# Shield_V4_Connector_All.net
KiCad netlist of a schematic drawn in EasyEDA
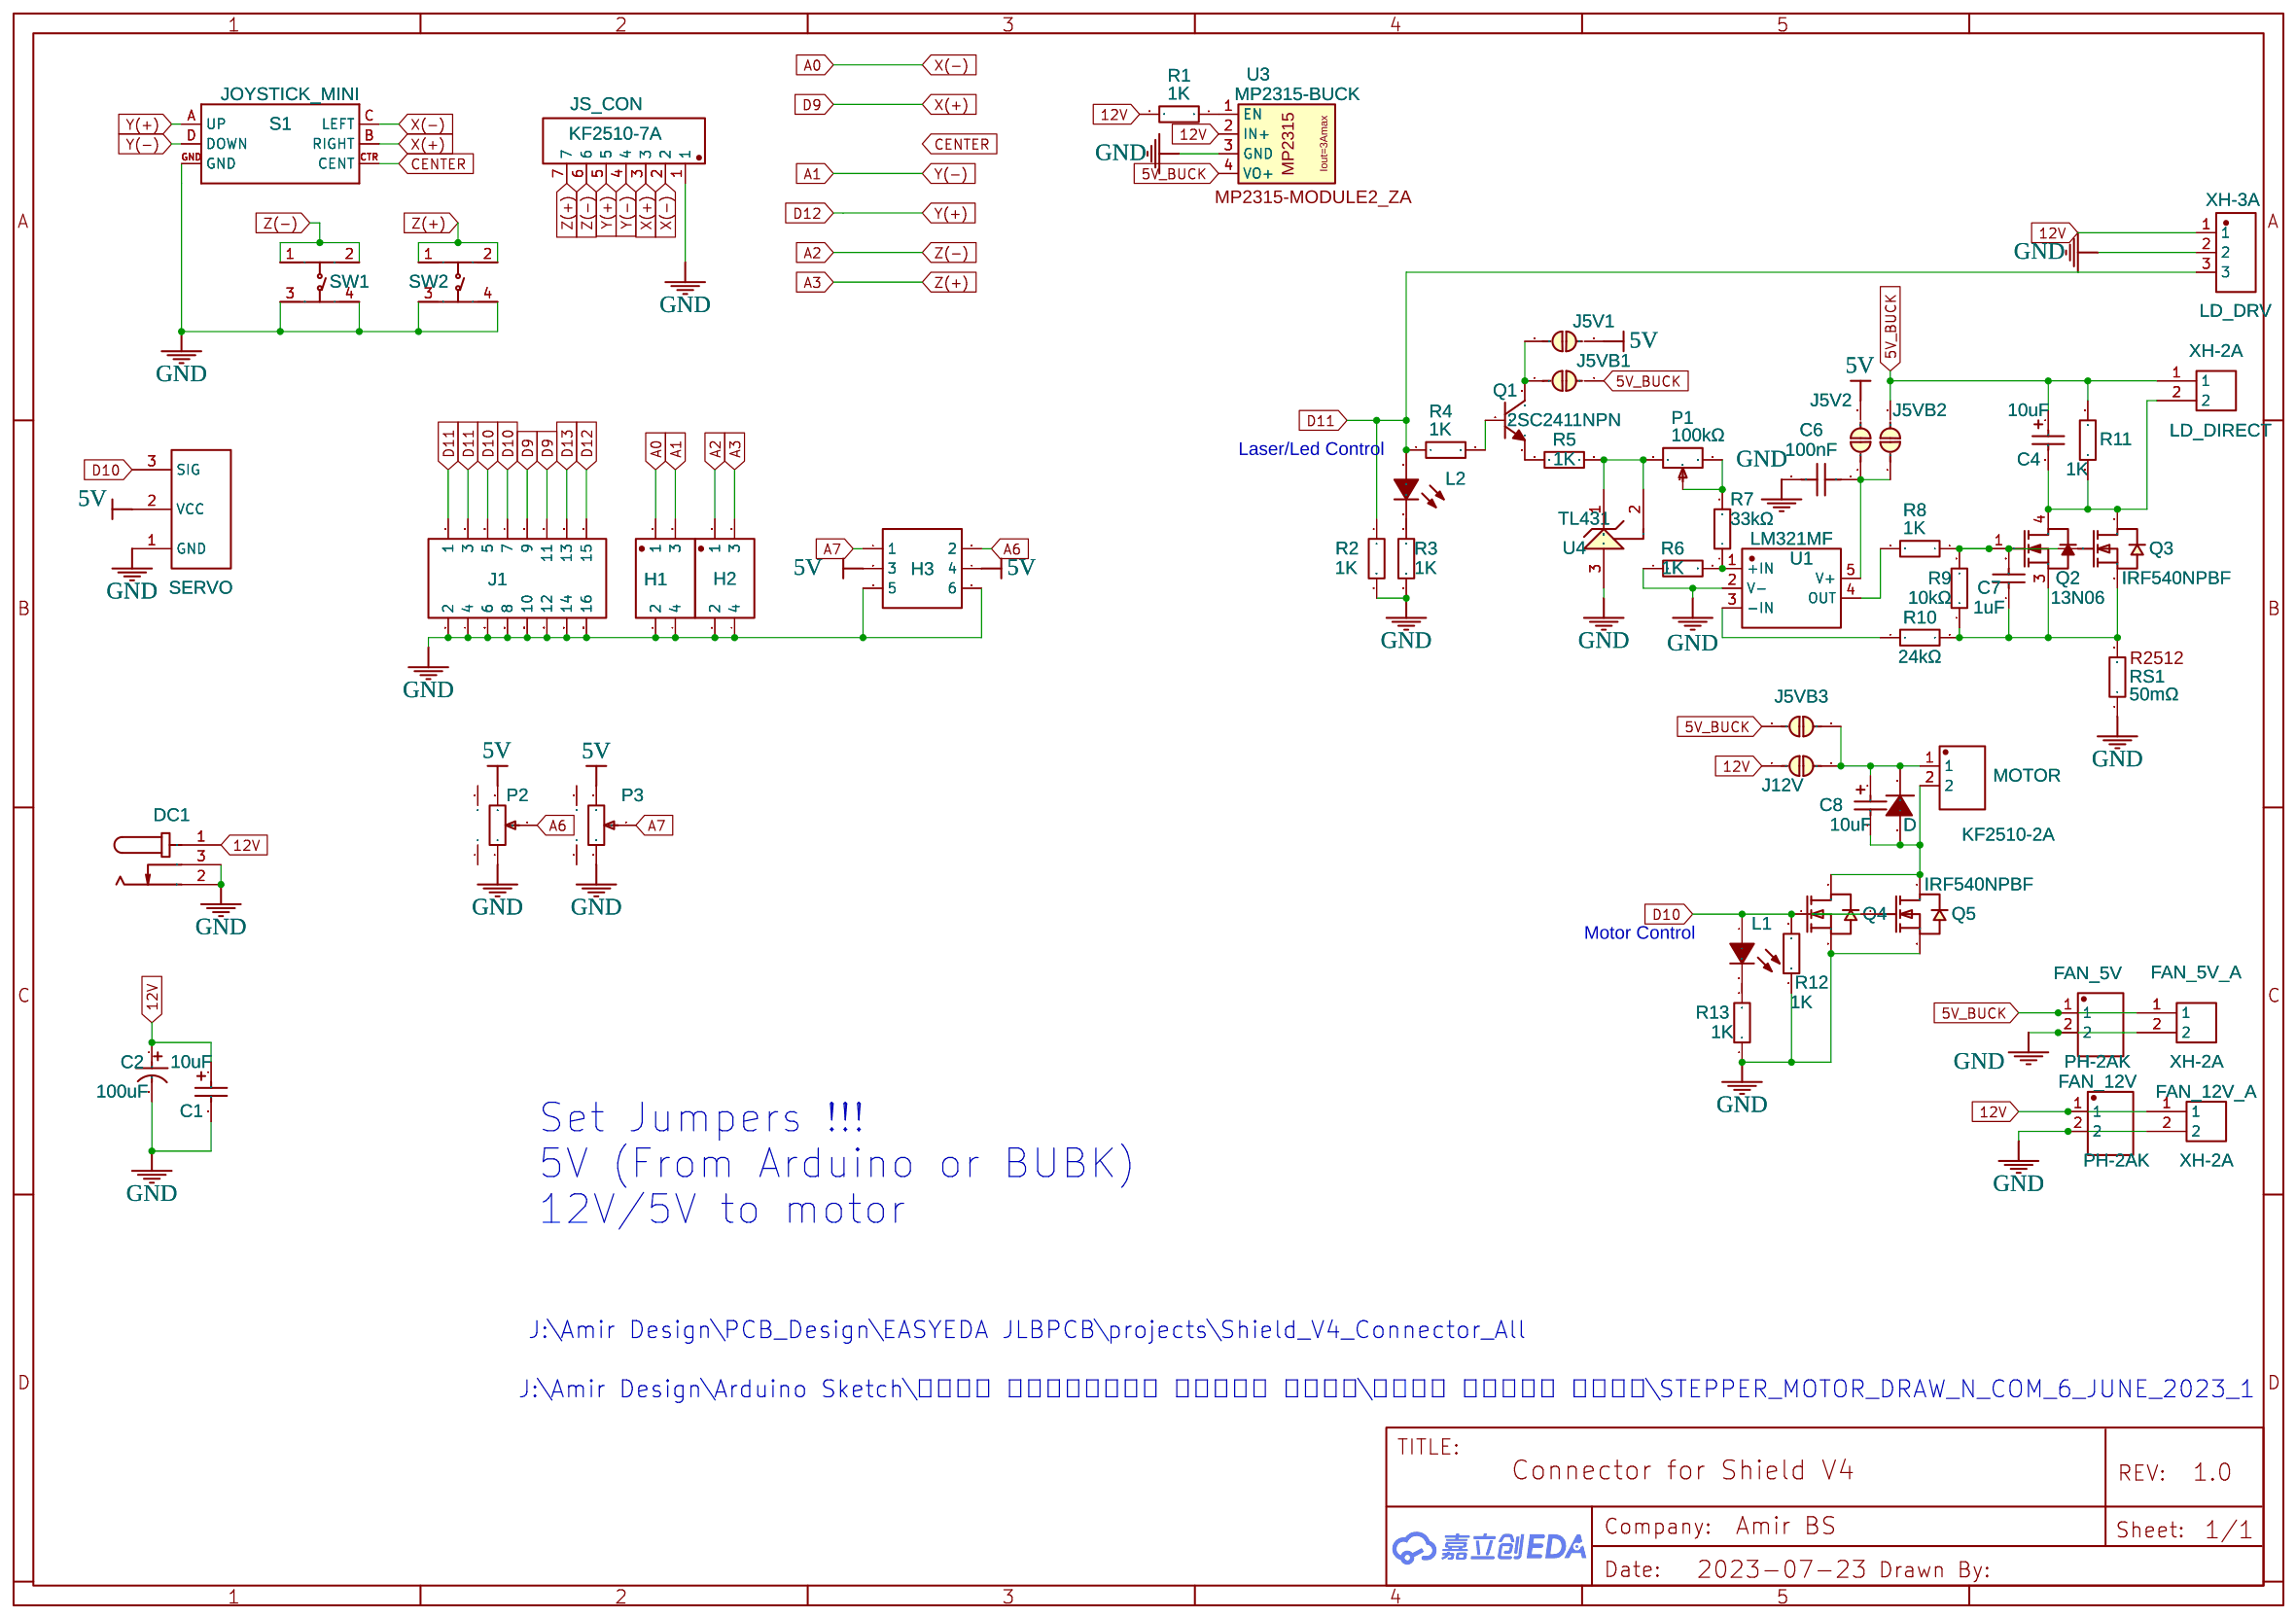
[diagram p0: schematic sheet]

(export (version "E")
  (design (tool "Eeschema 10.0.6"))
  (components
    (comp (ref "C1")
      (value "10uF")
      (fields (field (name "Manufacturer Part") "TAJA106K016RNJ") (field (name "Manufacturer") "Kyocera AVX"))
      (libsource (lib "") (part "TAJA106K016RNJ"))
    )
    (comp (ref "C2")
      (value "100uF")
      (fields
        (field (name "Manufacturer Part") "KM107M035E11RR0VH2FP0")
        (field (name "Manufacturer") "CX(承兴)")
      )
      (libsource (lib "") (part "100uF 35V 6.3*11"))
    )
    (comp (ref "C4")
      (value "10uF")
      (fields (field (name "Manufacturer Part") "TAJA106K016RNJ") (field (name "Manufacturer") "Kyocera AVX"))
      (libsource (lib "") (part "TAJA106K016RNJ"))
    )
    (comp (ref "C6")
      (value "100nF")
      (fields
        (field (name "BOM_Manufacturer Part") "CC0603KRX7R9BB104")
        (field (name "BOM_Supplier Part") "C14663")
      )
      (libsource (lib "") (part "CC0603KRX7R9BB104"))
    )
    (comp (ref "C7")
      (value "1uF")
      (fields
        (field (name "Manufacturer Part") "CL10A105KB8NNNC")
        (field (name "Manufacturer") "SAMSUNG(三星)")
      )
      (libsource (lib "") (part "CL10A105KB8NNNC"))
    )
    (comp (ref "C8")
      (value "10uF")
      (fields (field (name "Manufacturer Part") "TAJA106K016RNJ") (field (name "Manufacturer") "Kyocera AVX"))
      (libsource (lib "") (part "TAJA106K016RNJ"))
    )
    (comp (ref "D")
      (value "1N4007")
      (fields (field (name "BOM_Manufacturer Part") "1N4007F") (field (name "BOM_Supplier Part") "C110856"))
      (libsource (lib "") (part "1N4007F"))
    )
    (comp (ref "DC1")
      (value "DC")
      (fields
        (field (name "BOM_Manufacturer Part") "DC005-2.0MM")
        (field (name "BOM_Supplier Part") "C111567")
      )
      (libsource (lib "") (part "DC005-2.0MM"))
    )
    (comp (ref "FAN_5V")
      (value "PH-2AK")
      (fields (field (name "BOM_Supplier Part") "C8886"))
      (libsource (lib "") (part "PH-2AK_1"))
    )
    (comp (ref "FAN_5V_A")
      (value "XH-2A")
      (fields (field (name "Manufacturer") "BOOMELE(博穆精密)"))
      (libsource (lib "") (part "XH-2A"))
    )
    (comp (ref "FAN_12V")
      (value "PH-2AK")
      (fields (field (name "BOM_Supplier Part") "C8886"))
      (libsource (lib "") (part "PH-2AK"))
    )
    (comp (ref "FAN_12V_A")
      (value "XH-2A")
      (fields (field (name "Manufacturer") "BOOMELE(博穆精密)"))
      (libsource (lib "") (part "XH-2A_2"))
    )
    (comp (ref "H1")
      (value "Header-Female-2.54_2x2")
      (fields
        (field (name "BOM_Manufacturer Part") "DS1023-2*2SF11")
        (field (name "BOM_Supplier Part") "C92273")
      )
      (libsource (lib "") (part "Header-Female-2.54_2x2"))
    )
    (comp (ref "H2")
      (value "Header-Female-2.54_2x2")
      (fields
        (field (name "BOM_Manufacturer Part") "DS1023-2*2SF11")
        (field (name "BOM_Supplier Part") "C92273")
      )
      (libsource (lib "") (part "Header-Female-2.54_2x2"))
    )
    (comp (ref "H3")
      (value "Header-Female-2.54_2x3")
      (fields
        (field (name "BOM_Manufacturer Part") "DS1023-2*3SF11")
        (field (name "BOM_Supplier Part") "C92272")
      )
      (libsource (lib "") (part "Header-Female-2.54_2x3"))
    )
    (comp (ref "J1")
      (value "Header-Female-2.54_2x8")
      (fields (field (name "BOM_Manufacturer Part") "2.54-2*8P母") (field (name "BOM_Supplier Part") "C30734"))
      (libsource (lib "") (part "Header-Female-2.54_2x8"))
    )
    (comp (ref "J5V1") (value "JUMPER-SMT_2") (libsource (lib "") (part "JUMPER-SMT_2_1")))
    (comp (ref "J5V2") (value "JUMPER-SMT_2") (libsource (lib "") (part "JUMPER-SMT_2")))
    (comp (ref "J5VB1") (value "JUMPER-SMT_2") (libsource (lib "") (part "JUMPER-SMT_2_5")))
    (comp (ref "J5VB2") (value "JUMPER-SMT_2") (libsource (lib "") (part "JUMPER-SMT_2_4")))
    (comp (ref "J5VB3") (value "JUMPER-SMT_2") (libsource (lib "") (part "JUMPER-SMT_2_3")))
    (comp (ref "J12V") (value "JUMPER-SMT_2") (libsource (lib "") (part "JUMPER-SMT_2_2")))
    (comp (ref "JS_CON")
      (value "KF2510-7A")
      (fields (field (name "Manufacturer") "BOOMELE"))
      (libsource (lib "") (part "KF2510-7A"))
    )
    (comp (ref "L1")
      (value "LED")
      (fields
        (field (name "BOM_Manufacturer Part") "19-217/BHC-ZL1M2RY/3T")
        (field (name "BOM_Supplier Part") "C72041")
      )
      (libsource (lib "") (part "19-217/BHC-ZL1M2RY/3T"))
    )
    (comp (ref "L2")
      (value "LED")
      (fields
        (field (name "BOM_Manufacturer Part") "19-217/BHC-ZL1M2RY/3T")
        (field (name "BOM_Supplier Part") "C72041")
      )
      (libsource (lib "") (part "19-217/BHC-ZL1M2RY/3T"))
    )
    (comp (ref "LD_DIRECT")
      (value "XH-2A")
      (fields (field (name "Manufacturer") "BOOMELE(博穆精密)"))
      (libsource (lib "") (part "XH-2A_1"))
    )
    (comp (ref "LD_DRV")
      (value "XH-3A")
      (fields (field (name "Manufacturer") "HCTL(华灿天禄)"))
      (libsource (lib "") (part "XH-3A_C2908601"))
    )
    (comp (ref "MOTOR")
      (value "KF2510-2A")
      (fields (field (name "BOM_Supplier Part") "C27543"))
      (libsource (lib "") (part "KF2510-2A"))
    )
    (comp (ref "P1")
      (value "100kΩ")
      (fields (field (name "Manufacturer Part") "3296W-1-104LF") (field (name "Manufacturer") "BOURNS"))
      (libsource (lib "") (part "3296W-1-104LF"))
    )
    (comp (ref "P2")
      (value "长柄旋转电位器")
      (fields (field (name "BOM_Supplier Part") "C2874842"))
      (libsource (lib "") (part "长柄旋转电位器"))
    )
    (comp (ref "P3")
      (value "长柄旋转电位器")
      (fields (field (name "BOM_Supplier Part") "C2874842"))
      (libsource (lib "") (part "长柄旋转电位器"))
    )
    (comp (ref "Q1")
      (value "2SC2411NPN")
      (fields (field (name "Manufacturer Part") "2SC2411KT146R") (field (name "Manufacturer") "ROHM(罗姆)"))
      (libsource (lib "") (part "2SC2411KT146R"))
    )
    (comp (ref "Q2")
      (value "13N06")
      (fields (field (name "Manufacturer Part") "FQD13N06LTM") (field (name "Manufacturer") "onsemi(安森美)"))
      (libsource (lib "") (part "FQD13N06LTM"))
    )
    (comp (ref "Q3")
      (value "IRF540NPBF")
      (fields (field (name "Manufacturer") "Infineon(英飞凌)"))
      (libsource (lib "") (part "IRF540NPBF"))
    )
    (comp (ref "Q4")
      (value "Q")
      (fields (field (name "BOM_Manufacturer Part") "JSM2302") (field (name "BOM_Supplier Part") "C916403"))
      (libsource (lib "") (part "JSM2302"))
    )
    (comp (ref "Q5")
      (value "IRF540NPBF")
      (fields (field (name "Manufacturer") "Infineon(英飞凌)"))
      (libsource (lib "") (part "IRF540NPBF"))
    )
    (comp (ref "R1")
      (value "1K")
      (fields
        (field (name "BOM_Manufacturer Part") "0603WAF1001T5E")
        (field (name "BOM_Supplier Part") "C21190")
      )
      (libsource (lib "") (part "0603WAF1001T5E_2"))
    )
    (comp (ref "R2")
      (value "1K")
      (fields
        (field (name "BOM_Manufacturer Part") "0603WAF1001T5E")
        (field (name "BOM_Supplier Part") "C21190")
      )
      (libsource (lib "") (part "0603WAF1001T5E"))
    )
    (comp (ref "R3")
      (value "1K")
      (fields
        (field (name "BOM_Manufacturer Part") "0603WAF1001T5E")
        (field (name "BOM_Supplier Part") "C21190")
      )
      (libsource (lib "") (part "0603WAF1001T5E"))
    )
    (comp (ref "R4")
      (value "1K")
      (fields
        (field (name "BOM_Manufacturer Part") "0603WAF1001T5E")
        (field (name "BOM_Supplier Part") "C21190")
      )
      (libsource (lib "") (part "0603WAF1001T5E_1"))
    )
    (comp (ref "R5")
      (value "1K")
      (fields
        (field (name "BOM_Manufacturer Part") "0603WAF1001T5E")
        (field (name "BOM_Supplier Part") "C21190")
      )
      (libsource (lib "") (part "0603WAF1001T5E_2"))
    )
    (comp (ref "R6")
      (value "1K")
      (fields
        (field (name "BOM_Manufacturer Part") "0603WAF1001T5E")
        (field (name "BOM_Supplier Part") "C21190")
      )
      (libsource (lib "") (part "0603WAF1001T5E_1"))
    )
    (comp (ref "R7")
      (value "33kΩ")
      (fields
        (field (name "Manufacturer Part") "0603WAF3302T5E")
        (field (name "Manufacturer") "UNI-ROYAL(厚声)")
      )
      (libsource (lib "") (part "0603WAF3302T5E"))
    )
    (comp (ref "R8")
      (value "1K")
      (fields
        (field (name "BOM_Manufacturer Part") "0603WAF1001T5E")
        (field (name "BOM_Supplier Part") "C21190")
      )
      (libsource (lib "") (part "0603WAF1001T5E_2"))
    )
    (comp (ref "R9")
      (value "10kΩ")
      (fields
        (field (name "BOM_Manufacturer Part") "0603WAF1002T5E")
        (field (name "BOM_Supplier Part") "C25804")
      )
      (libsource (lib "") (part "0603WAF1002T5E"))
    )
    (comp (ref "R10")
      (value "24kΩ")
      (fields
        (field (name "Manufacturer Part") "0603WAF2402T5E")
        (field (name "Manufacturer") "UNI-ROYAL(厚声)")
      )
      (libsource (lib "") (part "0603WAF2402T5E"))
    )
    (comp (ref "R11")
      (value "1K")
      (fields
        (field (name "BOM_Manufacturer Part") "0603WAF1001T5E")
        (field (name "BOM_Supplier Part") "C21190")
      )
      (libsource (lib "") (part "0603WAF1001T5E_3"))
    )
    (comp (ref "R12")
      (value "1K")
      (fields
        (field (name "BOM_Manufacturer Part") "0603WAF1001T5E")
        (field (name "BOM_Supplier Part") "C21190")
      )
      (libsource (lib "") (part "0603WAF1001T5E_3"))
    )
    (comp (ref "R13")
      (value "1K")
      (fields
        (field (name "BOM_Manufacturer Part") "0603WAF1001T5E")
        (field (name "BOM_Supplier Part") "C21190")
      )
      (libsource (lib "") (part "0603WAF1001T5E_3"))
    )
    (comp (ref "RS1")
      (value "50mΩ")
      (fields
        (field (name "Manufacturer Part") "CR2512FR050E04R")
        (field (name "Manufacturer") "EVER OHMS(天二科技)")
      )
      (libsource (lib "") (part "CR2512F0R05E04"))
    )
    (comp (ref "S1") (value "JOYSTICK_MINI") (libsource (lib "") (part "JOYSTICK_MINI")))
    (comp (ref "SERVO")
      (value "Servo+3d")
      (fields (field (name "BOM_Manufacturer Part") "New SchematicLib"))
      (libsource (lib "") (part "Servo+3d"))
    )
    (comp (ref "SW1")
      (value "TC-6610-7-160G")
      (fields (field (name "Manufacturer") "HCTL(华灿天禄)"))
      (libsource (lib "") (part "TC-6610-7-160G"))
    )
    (comp (ref "SW2")
      (value "TC-6610-7-160G")
      (fields (field (name "Manufacturer") "HCTL(华灿天禄)"))
      (libsource (lib "") (part "TC-6610-7-160G"))
    )
    (comp (ref "U1")
      (value "LM321MF")
      (fields (field (name "Manufacturer") "UMW(广东友台半导体)"))
      (libsource (lib "") (part "LM321MF"))
    )
    (comp (ref "U3") (value "MP2315-BUCK") (libsource (lib "") (part "MP2315-BUCK")))
    (comp (ref "U4")
      (value "TL431")
      (fields (field (name "Manufacturer Part") "TL431BIDBZR") (field (name "Manufacturer") "TI(德州仪器)"))
      (libsource (lib "") (part "TL431BIDBZR"))
    )
  )
  (nets
    (net (code "1") (name "5V") (class "Default")
      (node (ref "H3") (pin "3") (pinfunction "3_3") (pintype "input"))
      (node (ref "H3") (pin "4") (pinfunction "4_4") (pintype "input"))
      (node (ref "J5V1") (pin "2") (pinfunction "2_2") (pintype "bidirectional"))
      (node (ref "J5V2") (pin "2") (pinfunction "2_2") (pintype "bidirectional"))
      (node (ref "P2") (pin "3") (pinfunction "3_3") (pintype "input"))
      (node (ref "P3") (pin "3") (pinfunction "3_3") (pintype "input"))
      (node (ref "SERVO") (pin "2") (pinfunction "VCC_2") (pintype "unspecified"))
    )
    (net (code "2") (name "5V_BUCK") (class "Default")
      (node (ref "C4") (pin "1") (pinfunction "1_1") (pintype "input"))
      (node (ref "FAN_5V") (pin "1") (pinfunction "1_1") (pintype "unspecified"))
      (node (ref "FAN_5V_A") (pin "1") (pinfunction "1_1") (pintype "unspecified"))
      (node (ref "J5VB1") (pin "2") (pinfunction "2_2") (pintype "bidirectional"))
      (node (ref "J5VB2") (pin "2") (pinfunction "2_2") (pintype "bidirectional"))
      (node (ref "J5VB3") (pin "2") (pinfunction "2_2") (pintype "bidirectional"))
      (node (ref "LD_DIRECT") (pin "1") (pinfunction "1_1") (pintype "unspecified"))
      (node (ref "R11") (pin "2") (pinfunction "2_2") (pintype "input"))
      (node (ref "U3") (pin "4") (pinfunction "VO+_4") (pintype "unspecified"))
    )
    (net (code "3") (name "12V") (class "Default")
      (node (ref "C1") (pin "1") (pinfunction "1_1") (pintype "input"))
      (node (ref "C2") (pin "1") (pinfunction "1_1") (pintype "input"))
      (node (ref "DC1") (pin "1") (pinfunction "1_1") (pintype "unspecified"))
      (node (ref "FAN_12V") (pin "1") (pinfunction "1_1") (pintype "unspecified"))
      (node (ref "FAN_12V_A") (pin "1") (pinfunction "1_1") (pintype "unspecified"))
      (node (ref "J12V") (pin "2") (pinfunction "2_2") (pintype "bidirectional"))
      (node (ref "LD_DRV") (pin "1") (pinfunction "1_1") (pintype "unspecified"))
      (node (ref "R1") (pin "2") (pinfunction "2_2") (pintype "input"))
      (node (ref "U3") (pin "2") (pinfunction "IN+_2") (pintype "unspecified"))
    )
    (net (code "4") (name "A0") (class "Default")
      (node (ref "H1") (pin "1") (pinfunction "1_1") (pintype "unspecified"))
      (node (ref "JS_CON") (pin "2") (pinfunction "2_2") (pintype "unspecified"))
      (node (ref "S1") (pin "C") (pinfunction "LEFT_C") (pintype "unspecified"))
    )
    (net (code "5") (name "A1") (class "Default")
      (node (ref "H1") (pin "3") (pinfunction "3_3") (pintype "unspecified"))
      (node (ref "JS_CON") (pin "4") (pinfunction "4_4") (pintype "unspecified"))
      (node (ref "S1") (pin "D") (pinfunction "DOWN_D") (pintype "unspecified"))
    )
    (net (code "6") (name "A2") (class "Default")
      (node (ref "H2") (pin "1") (pinfunction "1_1") (pintype "unspecified"))
      (node (ref "JS_CON") (pin "6") (pinfunction "6_6") (pintype "unspecified"))
      (node (ref "SW1") (pin "1") (pinfunction "1_1") (pintype "unspecified"))
      (node (ref "SW1") (pin "2") (pinfunction "2_2") (pintype "unspecified"))
    )
    (net (code "7") (name "A3") (class "Default")
      (node (ref "H2") (pin "3") (pinfunction "3_3") (pintype "unspecified"))
      (node (ref "JS_CON") (pin "7") (pinfunction "7_7") (pintype "unspecified"))
      (node (ref "SW2") (pin "1") (pinfunction "1_1") (pintype "unspecified"))
      (node (ref "SW2") (pin "2") (pinfunction "2_2") (pintype "unspecified"))
    )
    (net (code "8") (name "A6") (class "Default")
      (node (ref "H3") (pin "2") (pinfunction "2_2") (pintype "input"))
      (node (ref "P2") (pin "2") (pinfunction "2_2") (pintype "input"))
    )
    (net (code "9") (name "A7") (class "Default")
      (node (ref "H3") (pin "1") (pinfunction "1_1") (pintype "input"))
      (node (ref "P3") (pin "2") (pinfunction "2_2") (pintype "input"))
    )
    (net (code "10") (name "CENTER") (class "Default")
      (node (ref "S1") (pin "CTR") (pinfunction "CENT_CTR") (pintype "unspecified"))
    )
    (net (code "11") (name "D9") (class "Default")
      (node (ref "J1") (pin "11") (pinfunction "11_11") (pintype "input"))
      (node (ref "J1") (pin "9") (pinfunction "9_9") (pintype "input"))
      (node (ref "JS_CON") (pin "3") (pinfunction "3_3") (pintype "unspecified"))
      (node (ref "S1") (pin "B") (pinfunction "RIGHT_B") (pintype "unspecified"))
    )
    (net (code "12") (name "D10") (class "Default")
      (node (ref "J1") (pin "5") (pinfunction "5_5") (pintype "input"))
      (node (ref "J1") (pin "7") (pinfunction "7_7") (pintype "input"))
      (node (ref "L1") (pin "1") (pinfunction "A_1") (pintype "input"))
      (node (ref "Q4") (pin "1") (pinfunction "G_1") (pintype "unspecified"))
      (node (ref "Q5") (pin "1") (pinfunction "G_1") (pintype "unspecified"))
      (node (ref "R12") (pin "2") (pinfunction "2_2") (pintype "input"))
      (node (ref "SERVO") (pin "3") (pinfunction "SIG_3") (pintype "unspecified"))
    )
    (net (code "13") (name "D11") (class "Default")
      (node (ref "J1") (pin "1") (pinfunction "1_1") (pintype "input"))
      (node (ref "J1") (pin "3") (pinfunction "3_3") (pintype "input"))
      (node (ref "L2") (pin "1") (pinfunction "A_1") (pintype "input"))
      (node (ref "LD_DRV") (pin "3") (pinfunction "3_3") (pintype "unspecified"))
      (node (ref "R2") (pin "1") (pinfunction "1_1") (pintype "input"))
      (node (ref "R4") (pin "1") (pinfunction "1_1") (pintype "input"))
    )
    (net (code "14") (name "D12") (class "Default")
      (node (ref "J1") (pin "15") (pinfunction "15_15") (pintype "input"))
      (node (ref "JS_CON") (pin "5") (pinfunction "5_5") (pintype "unspecified"))
      (node (ref "S1") (pin "A") (pinfunction "UP_A") (pintype "unspecified"))
    )
    (net (code "15") (name "D13") (class "Default")
      (node (ref "J1") (pin "13") (pinfunction "13_13") (pintype "input"))
    )
    (net (code "16") (name "GND") (class "Default")
      (node (ref "C1") (pin "2") (pinfunction "2_2") (pintype "input"))
      (node (ref "C2") (pin "2") (pinfunction "2_2") (pintype "input"))
      (node (ref "C6") (pin "2") (pinfunction "2_2") (pintype "unspecified"))
      (node (ref "DC1") (pin "2") (pinfunction "2_2") (pintype "unspecified"))
      (node (ref "DC1") (pin "3") (pinfunction "3_3") (pintype "unspecified"))
      (node (ref "FAN_12V") (pin "2") (pinfunction "2_2") (pintype "unspecified"))
      (node (ref "FAN_12V_A") (pin "2") (pinfunction "2_2") (pintype "unspecified"))
      (node (ref "FAN_5V") (pin "2") (pinfunction "2_2") (pintype "unspecified"))
      (node (ref "FAN_5V_A") (pin "2") (pinfunction "2_2") (pintype "unspecified"))
      (node (ref "H1") (pin "2") (pinfunction "2_2") (pintype "unspecified"))
      (node (ref "H1") (pin "4") (pinfunction "4_4") (pintype "unspecified"))
      (node (ref "H2") (pin "2") (pinfunction "2_2") (pintype "unspecified"))
      (node (ref "H2") (pin "4") (pinfunction "4_4") (pintype "unspecified"))
      (node (ref "H3") (pin "5") (pinfunction "5_5") (pintype "input"))
      (node (ref "H3") (pin "6") (pinfunction "6_6") (pintype "input"))
      (node (ref "J1") (pin "10") (pinfunction "10_10") (pintype "input"))
      (node (ref "J1") (pin "12") (pinfunction "12_12") (pintype "input"))
      (node (ref "J1") (pin "14") (pinfunction "14_14") (pintype "input"))
      (node (ref "J1") (pin "16") (pinfunction "16_16") (pintype "input"))
      (node (ref "J1") (pin "2") (pinfunction "2_2") (pintype "input"))
      (node (ref "J1") (pin "4") (pinfunction "4_4") (pintype "input"))
      (node (ref "J1") (pin "6") (pinfunction "6_6") (pintype "input"))
      (node (ref "J1") (pin "8") (pinfunction "8_8") (pintype "input"))
      (node (ref "JS_CON") (pin "1") (pinfunction "1_1") (pintype "unspecified"))
      (node (ref "LD_DRV") (pin "2") (pinfunction "2_2") (pintype "unspecified"))
      (node (ref "P2") (pin "1") (pinfunction "1_1") (pintype "input"))
      (node (ref "P3") (pin "1") (pinfunction "1_1") (pintype "input"))
      (node (ref "Q4") (pin "2") (pinfunction "S_2") (pintype "unspecified"))
      (node (ref "Q5") (pin "3") (pinfunction "S_3") (pintype "unspecified"))
      (node (ref "R12") (pin "1") (pinfunction "1_1") (pintype "input"))
      (node (ref "R13") (pin "1") (pinfunction "1_1") (pintype "input"))
      (node (ref "R2") (pin "2") (pinfunction "2_2") (pintype "input"))
      (node (ref "R3") (pin "2") (pinfunction "2_2") (pintype "input"))
      (node (ref "R6") (pin "1") (pinfunction "1_1") (pintype "input"))
      (node (ref "RS1") (pin "1") (pinfunction "1_1") (pintype "unspecified"))
      (node (ref "S1") (pin "GND") (pinfunction "GND_GND") (pintype "unspecified"))
      (node (ref "SERVO") (pin "1") (pinfunction "GND_1") (pintype "unspecified"))
      (node (ref "SW1") (pin "3") (pinfunction "3_3") (pintype "unspecified"))
      (node (ref "SW1") (pin "4") (pinfunction "4_4") (pintype "unspecified"))
      (node (ref "SW2") (pin "3") (pinfunction "3_3") (pintype "unspecified"))
      (node (ref "SW2") (pin "4") (pinfunction "4_4") (pintype "unspecified"))
      (node (ref "U1") (pin "2") (pinfunction "V-_2") (pintype "unspecified"))
      (node (ref "U3") (pin "3") (pinfunction "GND_3") (pintype "unspecified"))
      (node (ref "U4") (pin "3") (pinfunction "ANODE_3") (pintype "unspecified"))
    )
    (net (code "17") (name "Net-(D-A)") (class "Default")
      (node (ref "C8") (pin "2") (pinfunction "2_2") (pintype "input"))
      (node (ref "D") (pin "2") (pinfunction "A_2") (pintype "unspecified"))
      (node (ref "MOTOR") (pin "2") (pinfunction "2_2") (pintype "unspecified"))
      (node (ref "Q4") (pin "3") (pinfunction "D_3") (pintype "unspecified"))
      (node (ref "Q5") (pin "2") (pinfunction "D_2") (pintype "unspecified"))
    )
    (net (code "18") (name "Net-(D-C)") (class "Default")
      (node (ref "C8") (pin "1") (pinfunction "1_1") (pintype "input"))
      (node (ref "D") (pin "1") (pinfunction "C_1") (pintype "unspecified"))
      (node (ref "J12V") (pin "1") (pinfunction "1_1") (pintype "bidirectional"))
      (node (ref "J5VB3") (pin "1") (pinfunction "1_1") (pintype "bidirectional"))
      (node (ref "MOTOR") (pin "1") (pinfunction "1_1") (pintype "unspecified"))
    )
    (net (code "19") (name "Net-(L1-C)") (class "Default")
      (node (ref "L1") (pin "2") (pinfunction "C_2") (pintype "input"))
      (node (ref "R13") (pin "2") (pinfunction "2_2") (pintype "input"))
    )
    (net (code "20") (name "Net-(L2-C)") (class "Default")
      (node (ref "L2") (pin "2") (pinfunction "C_2") (pintype "input"))
      (node (ref "R3") (pin "1") (pinfunction "1_1") (pintype "input"))
    )
    (net (code "21") (name "Net-(P1-Pad2)") (class "Default")
      (node (ref "P1") (pin "2") (pinfunction "2_2") (pintype "input"))
      (node (ref "P1") (pin "3") (pinfunction "3_3") (pintype "input"))
      (node (ref "R7") (pin "2") (pinfunction "2_2") (pintype "input"))
    )
    (net (code "22") (name "Net-(Q1-B)") (class "Default")
      (node (ref "Q1") (pin "2") (pinfunction "B_2") (pintype "unspecified"))
      (node (ref "R4") (pin "2") (pinfunction "2_2") (pintype "input"))
    )
    (net (code "23") (name "Net-(Q1-C)") (class "Default")
      (node (ref "J5V1") (pin "1") (pinfunction "1_1") (pintype "bidirectional"))
      (node (ref "J5VB1") (pin "1") (pinfunction "1_1") (pintype "bidirectional"))
      (node (ref "Q1") (pin "3") (pinfunction "C_3") (pintype "unspecified"))
    )
    (net (code "24") (name "Net-(Q1-E)") (class "Default")
      (node (ref "Q1") (pin "1") (pinfunction "E_1") (pintype "unspecified"))
      (node (ref "R5") (pin "2") (pinfunction "2_2") (pintype "input"))
    )
    (net (code "25") (name "Net-(Q2-D)") (class "Default")
      (node (ref "C4") (pin "2") (pinfunction "2_2") (pintype "input"))
      (node (ref "LD_DIRECT") (pin "2") (pinfunction "2_2") (pintype "unspecified"))
      (node (ref "Q2") (pin "4") (pinfunction "D_4") (pintype "unspecified"))
      (node (ref "Q3") (pin "2") (pinfunction "D_2") (pintype "unspecified"))
      (node (ref "R11") (pin "1") (pinfunction "1_1") (pintype "input"))
    )
    (net (code "26") (name "Net-(Q2-G)") (class "Default")
      (node (ref "C7") (pin "2") (pinfunction "2_2") (pintype "input"))
      (node (ref "Q2") (pin "1") (pinfunction "G_1") (pintype "unspecified"))
      (node (ref "Q3") (pin "1") (pinfunction "G_1") (pintype "unspecified"))
      (node (ref "R8") (pin "1") (pinfunction "1_1") (pintype "input"))
      (node (ref "R9") (pin "2") (pinfunction "2_2") (pintype "input"))
    )
    (net (code "27") (name "Net-(Q2-S)") (class "Default")
      (node (ref "C7") (pin "1") (pinfunction "1_1") (pintype "input"))
      (node (ref "Q2") (pin "3") (pinfunction "S_3") (pintype "unspecified"))
      (node (ref "Q3") (pin "3") (pinfunction "S_3") (pintype "unspecified"))
      (node (ref "R10") (pin "2") (pinfunction "2_2") (pintype "input"))
      (node (ref "R9") (pin "1") (pinfunction "1_1") (pintype "input"))
      (node (ref "RS1") (pin "2") (pinfunction "2_2") (pintype "unspecified"))
    )
    (net (code "28") (name "Net-(U1-+IN)") (class "Default")
      (node (ref "R6") (pin "2") (pinfunction "2_2") (pintype "input"))
      (node (ref "R7") (pin "1") (pinfunction "1_1") (pintype "input"))
      (node (ref "U1") (pin "1") (pinfunction "+IN_1") (pintype "unspecified"))
    )
    (net (code "29") (name "Net-(U1--IN)") (class "Default")
      (node (ref "R10") (pin "1") (pinfunction "1_1") (pintype "input"))
      (node (ref "U1") (pin "3") (pinfunction "-IN_3") (pintype "unspecified"))
    )
    (net (code "30") (name "Net-(U1-OUT)") (class "Default")
      (node (ref "R8") (pin "2") (pinfunction "2_2") (pintype "input"))
      (node (ref "U1") (pin "4") (pinfunction "OUT_4") (pintype "unspecified"))
    )
    (net (code "31") (name "Net-(U1-V+)") (class "Default")
      (node (ref "C6") (pin "1") (pinfunction "1_1") (pintype "unspecified"))
      (node (ref "J5V2") (pin "1") (pinfunction "1_1") (pintype "bidirectional"))
      (node (ref "J5VB2") (pin "1") (pinfunction "1_1") (pintype "bidirectional"))
      (node (ref "U1") (pin "5") (pinfunction "V+_5") (pintype "unspecified"))
    )
    (net (code "32") (name "Net-(U3-EN)") (class "Default")
      (node (ref "R1") (pin "1") (pinfunction "1_1") (pintype "input"))
      (node (ref "U3") (pin "1") (pinfunction "EN_1") (pintype "unspecified"))
    )
    (net (code "33") (name "Net-(U4-CATHODE)") (class "Default")
      (node (ref "P1") (pin "1") (pinfunction "1_1") (pintype "input"))
      (node (ref "R5") (pin "1") (pinfunction "1_1") (pintype "input"))
      (node (ref "U4") (pin "1") (pinfunction "CATHODE_1") (pintype "unspecified"))
      (node (ref "U4") (pin "2") (pinfunction "REF_2") (pintype "unspecified"))
    )
    (net (code "34") (name "unconnected-(P2-Pad4)") (class "Default")
      (node (ref "P2") (pin "4") (pinfunction "4_4") (pintype "input"))
    )
    (net (code "35") (name "unconnected-(P2-Pad5)") (class "Default")
      (node (ref "P2") (pin "5") (pinfunction "5_5") (pintype "input"))
    )
    (net (code "36") (name "unconnected-(P3-Pad4)") (class "Default")
      (node (ref "P3") (pin "4") (pinfunction "4_4") (pintype "input"))
    )
    (net (code "37") (name "unconnected-(P3-Pad5)") (class "Default")
      (node (ref "P3") (pin "5") (pinfunction "5_5") (pintype "input"))
    )
  )
)
